# clock.net
KiCad netlist of a schematic drawn in EAGLE
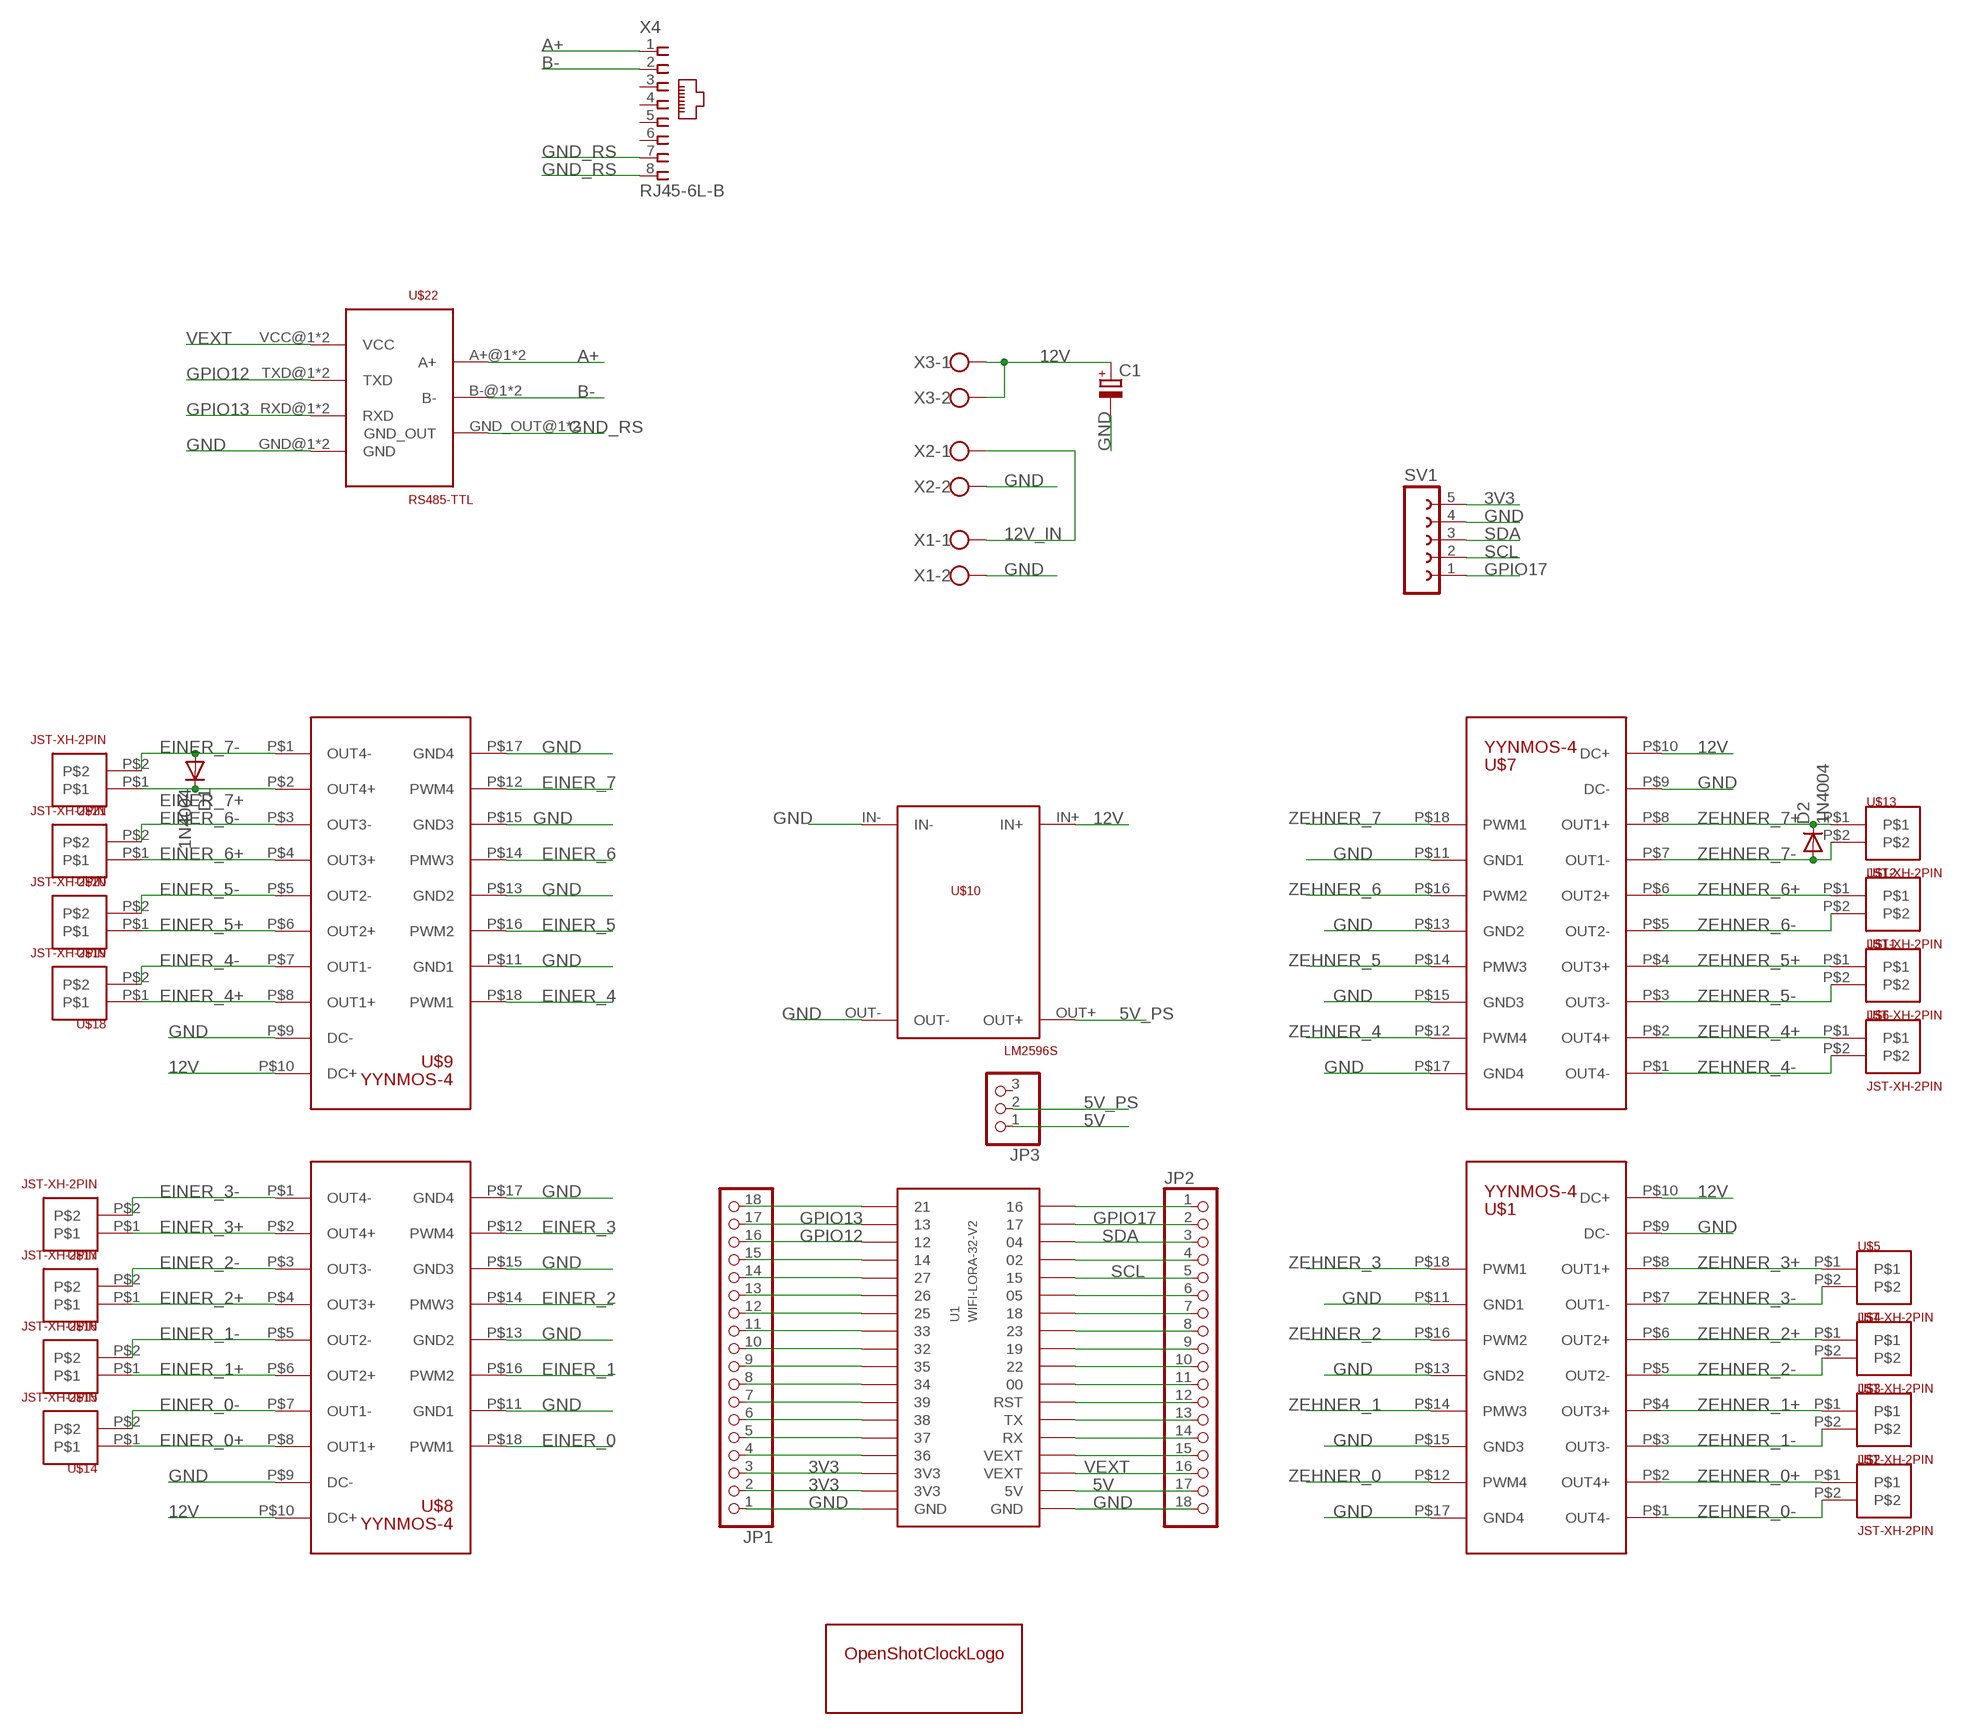
[diagram p0: schematic, sheet 1, part 1 of 2]
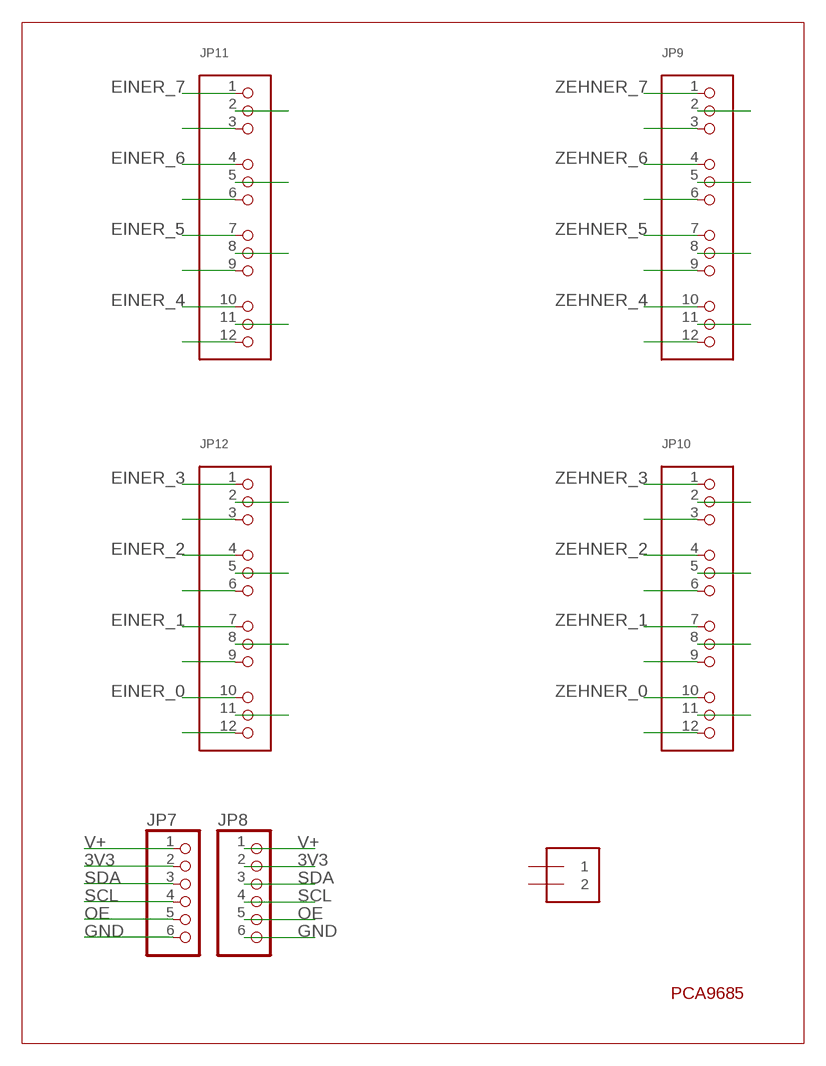
[diagram p1: schematic, sheet 1, part 2 of 2]

(export (version "E")
  (design (tool "Eeschema 10.0.6"))
  (components
    (comp (ref "C1")
      (value "CPOL-EUE2.5-6")
      (footprint "eagle-import:E2,5-6")
      (libsource (lib "eagle-import") (part "CPOL-EUE2.5-6"))
    )
    (comp (ref "D1")
      (value "1N4004")
      (footprint "eagle-import:DO41-10")
      (libsource (lib "eagle-import") (part "1N4004"))
    )
    (comp (ref "D2")
      (value "1N4004")
      (footprint "eagle-import:DO41-10")
      (libsource (lib "eagle-import") (part "1N4004"))
    )
    (comp (ref "J2")
      (value "TERMBLOCK_1X2-3.5MM")
      (footprint "eagle-import:1X2-3.5MM")
      (libsource (lib "eagle-import") (part "TERMBLOCK_1X2-3.5MM"))
    )
    (comp (ref "JP1")
      (value "PINHD-1X18")
      (footprint "eagle-import:1X18")
      (libsource (lib "eagle-import") (part "PINHD-1X18"))
    )
    (comp (ref "JP2")
      (value "PINHD-1X18")
      (footprint "eagle-import:1X18")
      (libsource (lib "eagle-import") (part "PINHD-1X18"))
    )
    (comp (ref "JP3")
      (value "PINHD-1X3")
      (footprint "eagle-import:1X03")
      (libsource (lib "eagle-import") (part "PINHD-1X3"))
    )
    (comp (ref "JP7")
      (value "PINHD-1X6CB")
      (footprint "eagle-import:1X06-CLEANBIG")
      (libsource (lib "eagle-import") (part "PINHD-1X6CB"))
    )
    (comp (ref "JP8")
      (value "PINHD-1X6CB")
      (footprint "eagle-import:1X06-CLEANBIG")
      (libsource (lib "eagle-import") (part "PINHD-1X6CB"))
    )
    (comp (ref "JP9")
      (value "HEADER-3X04")
      (footprint "eagle-import:3X04")
      (libsource (lib "eagle-import") (part "HEADER-3X04"))
    )
    (comp (ref "JP10")
      (value "HEADER-3X04")
      (footprint "eagle-import:3X04")
      (libsource (lib "eagle-import") (part "HEADER-3X04"))
    )
    (comp (ref "JP11")
      (value "HEADER-3X04")
      (footprint "eagle-import:3X04")
      (libsource (lib "eagle-import") (part "HEADER-3X04"))
    )
    (comp (ref "JP12")
      (value "HEADER-3X04")
      (footprint "eagle-import:3X04")
      (libsource (lib "eagle-import") (part "HEADER-3X04"))
    )
    (comp (ref "SV1")
      (value "FE05-1")
      (footprint "eagle-import:FE05-1")
      (libsource (lib "eagle-import") (part "FE05-1"))
    )
    (comp (ref "U$1")
      (value "YYNMOS-4")
      (footprint "eagle-import:YYNMOS-4")
      (libsource (lib "eagle-import") (part "YYNMOS-4"))
    )
    (comp (ref "U$2")
      (value "JST-XH-2PIN")
      (footprint "eagle-import:JST-XH-2PIN")
      (libsource (lib "eagle-import") (part "JST-XH-2PIN"))
    )
    (comp (ref "U$3")
      (value "JST-XH-2PIN")
      (footprint "eagle-import:JST-XH-2PIN")
      (libsource (lib "eagle-import") (part "JST-XH-2PIN"))
    )
    (comp (ref "U$4")
      (value "JST-XH-2PIN")
      (footprint "eagle-import:JST-XH-2PIN")
      (libsource (lib "eagle-import") (part "JST-XH-2PIN"))
    )
    (comp (ref "U$5")
      (value "JST-XH-2PIN")
      (footprint "eagle-import:JST-XH-2PIN")
      (libsource (lib "eagle-import") (part "JST-XH-2PIN"))
    )
    (comp (ref "U$6")
      (value "JST-XH-2PIN")
      (footprint "eagle-import:JST-XH-2PIN")
      (libsource (lib "eagle-import") (part "JST-XH-2PIN"))
    )
    (comp (ref "U$7")
      (value "YYNMOS-4")
      (footprint "eagle-import:YYNMOS-4")
      (libsource (lib "eagle-import") (part "YYNMOS-4"))
    )
    (comp (ref "U$8")
      (value "YYNMOS-4")
      (footprint "eagle-import:YYNMOS-4")
      (libsource (lib "eagle-import") (part "YYNMOS-4"))
    )
    (comp (ref "U$9")
      (value "YYNMOS-4")
      (footprint "eagle-import:YYNMOS-4")
      (libsource (lib "eagle-import") (part "YYNMOS-4"))
    )
    (comp (ref "U$10")
      (value "LM2596S")
      (footprint "eagle-import:LM2596S")
      (libsource (lib "eagle-import") (part "LM2596S"))
    )
    (comp (ref "U$11")
      (value "JST-XH-2PIN")
      (footprint "eagle-import:JST-XH-2PIN")
      (libsource (lib "eagle-import") (part "JST-XH-2PIN"))
    )
    (comp (ref "U$12")
      (value "JST-XH-2PIN")
      (footprint "eagle-import:JST-XH-2PIN")
      (libsource (lib "eagle-import") (part "JST-XH-2PIN"))
    )
    (comp (ref "U$13")
      (value "JST-XH-2PIN")
      (footprint "eagle-import:JST-XH-2PIN")
      (libsource (lib "eagle-import") (part "JST-XH-2PIN"))
    )
    (comp (ref "U$14")
      (value "JST-XH-2PIN")
      (footprint "eagle-import:JST-XH-2PIN")
      (libsource (lib "eagle-import") (part "JST-XH-2PIN"))
    )
    (comp (ref "U$15")
      (value "JST-XH-2PIN")
      (footprint "eagle-import:JST-XH-2PIN")
      (libsource (lib "eagle-import") (part "JST-XH-2PIN"))
    )
    (comp (ref "U$16")
      (value "JST-XH-2PIN")
      (footprint "eagle-import:JST-XH-2PIN")
      (libsource (lib "eagle-import") (part "JST-XH-2PIN"))
    )
    (comp (ref "U$17")
      (value "JST-XH-2PIN")
      (footprint "eagle-import:JST-XH-2PIN")
      (libsource (lib "eagle-import") (part "JST-XH-2PIN"))
    )
    (comp (ref "U$18")
      (value "JST-XH-2PIN")
      (footprint "eagle-import:JST-XH-2PIN")
      (libsource (lib "eagle-import") (part "JST-XH-2PIN"))
    )
    (comp (ref "U$19")
      (value "JST-XH-2PIN")
      (footprint "eagle-import:JST-XH-2PIN")
      (libsource (lib "eagle-import") (part "JST-XH-2PIN"))
    )
    (comp (ref "U$20")
      (value "JST-XH-2PIN")
      (footprint "eagle-import:JST-XH-2PIN")
      (libsource (lib "eagle-import") (part "JST-XH-2PIN"))
    )
    (comp (ref "U$21")
      (value "JST-XH-2PIN")
      (footprint "eagle-import:JST-XH-2PIN")
      (libsource (lib "eagle-import") (part "JST-XH-2PIN"))
    )
    (comp (ref "U$22")
      (value "RS485-TTL")
      (footprint "eagle-import:RS485-TTL")
      (libsource (lib "eagle-import") (part "RS485-TTL"))
    )
    (comp (ref "U$23")
      (value "OPEN-SHOT-CLOCK-LOGO")
      (footprint "eagle-import:OPEN-SHOT-CLOCK-LOGO")
      (libsource (lib "eagle-import") (part "OPEN-SHOT-CLOCK-LOGO"))
    )
    (comp (ref "U1")
      (value "WIFI-LORA-32-V2")
      (footprint "eagle-import:2.54MM_2X18")
      (libsource (lib "eagle-import") (part "WIFI-LORA-32-V2"))
    )
    (comp (ref "X1")
      (value "W237-102")
      (footprint "eagle-import:W237-102")
      (fields (field (name "MPN") "237-102"))
      (libsource (lib "eagle-import") (part "W237-102"))
    )
    (comp (ref "X2")
      (value "W237-102")
      (footprint "eagle-import:W237-102")
      (fields (field (name "MPN") "237-102"))
      (libsource (lib "eagle-import") (part "W237-102"))
    )
    (comp (ref "X3")
      (value "W237-102")
      (footprint "eagle-import:W237-102")
      (fields (field (name "MPN") "237-102"))
      (libsource (lib "eagle-import") (part "W237-102"))
    )
    (comp (ref "X4")
      (value "RJ45-6L-B")
      (footprint "eagle-import:RJ45-NO-SHIELD")
      (libsource (lib "eagle-import") (part "RJ45-6L-B"))
    )
  )
  (nets
    (net (code "1") (name "/3V3") (class "Default")
      (node (ref "JP1") (pin "2") (pinfunction "2_2") (pintype "passive"))
      (node (ref "JP1") (pin "3") (pinfunction "3_3") (pintype "passive"))
      (node (ref "JP7") (pin "2") (pinfunction "2_2") (pintype "passive"))
      (node (ref "JP8") (pin "2") (pinfunction "2_2") (pintype "passive"))
      (node (ref "SV1") (pin "5") (pinfunction "5_5") (pintype "passive"))
      (node (ref "U1") (pin "P$34") (pinfunction "3V3_P$34") (pintype "power_in"))
      (node (ref "U1") (pin "P$35") (pinfunction "3V3_P$35") (pintype "power_in"))
    )
    (net (code "2") (name "/5V") (class "Default")
      (node (ref "JP2") (pin "17") (pinfunction "17_17") (pintype "passive"))
      (node (ref "JP3") (pin "1") (pinfunction "1_1") (pintype "passive"))
      (node (ref "U1") (pin "P$2") (pinfunction "5V_P$2") (pintype "power_in"))
    )
    (net (code "3") (name "/5V_PS") (class "Default")
      (node (ref "JP3") (pin "2") (pinfunction "2_2") (pintype "passive"))
      (node (ref "U$10") (pin "OUT+") (pinfunction "OUT+_OUT+") (pintype "bidirectional"))
    )
    (net (code "4") (name "/12V") (class "Default")
      (node (ref "C1") (pin "+") (pinfunction "+_+") (pintype "passive"))
      (node (ref "U$1") (pin "P$10") (pinfunction "DC+_P$10") (pintype "bidirectional"))
      (node (ref "U$10") (pin "IN+") (pinfunction "IN+_IN+") (pintype "bidirectional"))
      (node (ref "U$7") (pin "P$10") (pinfunction "DC+_P$10") (pintype "bidirectional"))
      (node (ref "U$8") (pin "P$10") (pinfunction "DC+_P$10") (pintype "bidirectional"))
      (node (ref "U$9") (pin "P$10") (pinfunction "DC+_P$10") (pintype "bidirectional"))
      (node (ref "X3") (pin "1") (pinfunction "KL_1") (pintype "passive"))
      (node (ref "X3") (pin "2") (pinfunction "KL_2") (pintype "passive"))
    )
    (net (code "5") (name "/12V_IN") (class "Default")
      (node (ref "X1") (pin "1") (pinfunction "KL_1") (pintype "passive"))
      (node (ref "X2") (pin "1") (pinfunction "KL_1") (pintype "passive"))
    )
    (net (code "6") (name "/A+") (class "Default")
      (node (ref "U$22") (pin "A+@1") (pinfunction "A+_A+@1") (pintype "bidirectional"))
      (node (ref "U$22") (pin "A+@2") (pinfunction "A+_A+@2") (pintype "bidirectional"))
      (node (ref "X4") (pin "1") (pinfunction "1_1") (pintype "passive"))
    )
    (net (code "7") (name "/B-") (class "Default")
      (node (ref "U$22") (pin "B-@1") (pinfunction "B-_B-@1") (pintype "bidirectional"))
      (node (ref "U$22") (pin "B-@2") (pinfunction "B-_B-@2") (pintype "bidirectional"))
      (node (ref "X4") (pin "2") (pinfunction "2_2") (pintype "passive"))
    )
    (net (code "8") (name "/EINER_0") (class "Default")
      (node (ref "JP12") (pin "10") (pinfunction "10_10") (pintype "passive"))
      (node (ref "U$8") (pin "P$18") (pinfunction "PWM1_P$18") (pintype "bidirectional"))
    )
    (net (code "9") (name "/EINER_0+") (class "Default")
      (node (ref "U$14") (pin "P$1") (pinfunction "P$1_P$1") (pintype "bidirectional"))
      (node (ref "U$8") (pin "P$8") (pinfunction "OUT1+_P$8") (pintype "bidirectional"))
    )
    (net (code "10") (name "/EINER_0-") (class "Default")
      (node (ref "U$14") (pin "P$2") (pinfunction "P$2_P$2") (pintype "bidirectional"))
      (node (ref "U$8") (pin "P$7") (pinfunction "OUT1-_P$7") (pintype "bidirectional"))
    )
    (net (code "11") (name "/EINER_1") (class "Default")
      (node (ref "JP12") (pin "7") (pinfunction "7_7") (pintype "passive"))
      (node (ref "U$8") (pin "P$16") (pinfunction "PWM2_P$16") (pintype "bidirectional"))
    )
    (net (code "12") (name "/EINER_1+") (class "Default")
      (node (ref "U$15") (pin "P$1") (pinfunction "P$1_P$1") (pintype "bidirectional"))
      (node (ref "U$8") (pin "P$6") (pinfunction "OUT2+_P$6") (pintype "bidirectional"))
    )
    (net (code "13") (name "/EINER_1-") (class "Default")
      (node (ref "U$15") (pin "P$2") (pinfunction "P$2_P$2") (pintype "bidirectional"))
      (node (ref "U$8") (pin "P$5") (pinfunction "OUT2-_P$5") (pintype "bidirectional"))
    )
    (net (code "14") (name "/EINER_2") (class "Default")
      (node (ref "JP12") (pin "4") (pinfunction "4_4") (pintype "passive"))
      (node (ref "U$8") (pin "P$14") (pinfunction "PMW3_P$14") (pintype "bidirectional"))
    )
    (net (code "15") (name "/EINER_2+") (class "Default")
      (node (ref "U$16") (pin "P$1") (pinfunction "P$1_P$1") (pintype "bidirectional"))
      (node (ref "U$8") (pin "P$4") (pinfunction "OUT3+_P$4") (pintype "bidirectional"))
    )
    (net (code "16") (name "/EINER_2-") (class "Default")
      (node (ref "U$16") (pin "P$2") (pinfunction "P$2_P$2") (pintype "bidirectional"))
      (node (ref "U$8") (pin "P$3") (pinfunction "OUT3-_P$3") (pintype "bidirectional"))
    )
    (net (code "17") (name "/EINER_3") (class "Default")
      (node (ref "JP12") (pin "1") (pinfunction "1_1") (pintype "passive"))
      (node (ref "U$8") (pin "P$12") (pinfunction "PWM4_P$12") (pintype "bidirectional"))
    )
    (net (code "18") (name "/EINER_3+") (class "Default")
      (node (ref "U$17") (pin "P$1") (pinfunction "P$1_P$1") (pintype "bidirectional"))
      (node (ref "U$8") (pin "P$2") (pinfunction "OUT4+_P$2") (pintype "bidirectional"))
    )
    (net (code "19") (name "/EINER_3-") (class "Default")
      (node (ref "U$17") (pin "P$2") (pinfunction "P$2_P$2") (pintype "bidirectional"))
      (node (ref "U$8") (pin "P$1") (pinfunction "OUT4-_P$1") (pintype "bidirectional"))
    )
    (net (code "20") (name "/EINER_4") (class "Default")
      (node (ref "JP11") (pin "10") (pinfunction "10_10") (pintype "passive"))
      (node (ref "U$9") (pin "P$18") (pinfunction "PWM1_P$18") (pintype "bidirectional"))
    )
    (net (code "21") (name "/EINER_4+") (class "Default")
      (node (ref "U$18") (pin "P$1") (pinfunction "P$1_P$1") (pintype "bidirectional"))
      (node (ref "U$9") (pin "P$8") (pinfunction "OUT1+_P$8") (pintype "bidirectional"))
    )
    (net (code "22") (name "/EINER_4-") (class "Default")
      (node (ref "U$18") (pin "P$2") (pinfunction "P$2_P$2") (pintype "bidirectional"))
      (node (ref "U$9") (pin "P$7") (pinfunction "OUT1-_P$7") (pintype "bidirectional"))
    )
    (net (code "23") (name "/EINER_5") (class "Default")
      (node (ref "JP11") (pin "7") (pinfunction "7_7") (pintype "passive"))
      (node (ref "U$9") (pin "P$16") (pinfunction "PWM2_P$16") (pintype "bidirectional"))
    )
    (net (code "24") (name "/EINER_5+") (class "Default")
      (node (ref "U$19") (pin "P$1") (pinfunction "P$1_P$1") (pintype "bidirectional"))
      (node (ref "U$9") (pin "P$6") (pinfunction "OUT2+_P$6") (pintype "bidirectional"))
    )
    (net (code "25") (name "/EINER_5-") (class "Default")
      (node (ref "U$19") (pin "P$2") (pinfunction "P$2_P$2") (pintype "bidirectional"))
      (node (ref "U$9") (pin "P$5") (pinfunction "OUT2-_P$5") (pintype "bidirectional"))
    )
    (net (code "26") (name "/EINER_6") (class "Default")
      (node (ref "JP11") (pin "4") (pinfunction "4_4") (pintype "passive"))
      (node (ref "U$9") (pin "P$14") (pinfunction "PMW3_P$14") (pintype "bidirectional"))
    )
    (net (code "27") (name "/EINER_6+") (class "Default")
      (node (ref "U$20") (pin "P$1") (pinfunction "P$1_P$1") (pintype "bidirectional"))
      (node (ref "U$9") (pin "P$4") (pinfunction "OUT3+_P$4") (pintype "bidirectional"))
    )
    (net (code "28") (name "/EINER_6-") (class "Default")
      (node (ref "U$20") (pin "P$2") (pinfunction "P$2_P$2") (pintype "bidirectional"))
      (node (ref "U$9") (pin "P$3") (pinfunction "OUT3-_P$3") (pintype "bidirectional"))
    )
    (net (code "29") (name "/EINER_7") (class "Default")
      (node (ref "JP11") (pin "1") (pinfunction "1_1") (pintype "passive"))
      (node (ref "U$9") (pin "P$12") (pinfunction "PWM4_P$12") (pintype "bidirectional"))
    )
    (net (code "30") (name "/EINER_7+") (class "Default")
      (node (ref "D1") (pin "C") (pinfunction "C_C") (pintype "passive"))
      (node (ref "U$21") (pin "P$1") (pinfunction "P$1_P$1") (pintype "bidirectional"))
      (node (ref "U$9") (pin "P$2") (pinfunction "OUT4+_P$2") (pintype "bidirectional"))
    )
    (net (code "31") (name "/EINER_7-") (class "Default")
      (node (ref "D1") (pin "A") (pinfunction "A_A") (pintype "passive"))
      (node (ref "U$21") (pin "P$2") (pinfunction "P$2_P$2") (pintype "bidirectional"))
      (node (ref "U$9") (pin "P$1") (pinfunction "OUT4-_P$1") (pintype "bidirectional"))
    )
    (net (code "32") (name "/GND") (class "Default")
      (node (ref "C1") (pin "-") (pinfunction "-_-") (pintype "passive"))
      (node (ref "JP1") (pin "1") (pinfunction "1_1") (pintype "passive"))
      (node (ref "JP2") (pin "18") (pinfunction "18_18") (pintype "passive"))
      (node (ref "JP7") (pin "6") (pinfunction "6_6") (pintype "passive"))
      (node (ref "JP8") (pin "6") (pinfunction "6_6") (pintype "passive"))
      (node (ref "SV1") (pin "4") (pinfunction "4_4") (pintype "passive"))
      (node (ref "U$1") (pin "P$11") (pinfunction "GND1_P$11") (pintype "bidirectional"))
      (node (ref "U$1") (pin "P$13") (pinfunction "GND2_P$13") (pintype "bidirectional"))
      (node (ref "U$1") (pin "P$15") (pinfunction "GND3_P$15") (pintype "bidirectional"))
      (node (ref "U$1") (pin "P$17") (pinfunction "GND4_P$17") (pintype "bidirectional"))
      (node (ref "U$1") (pin "P$9") (pinfunction "DC-_P$9") (pintype "bidirectional"))
      (node (ref "U$10") (pin "IN-") (pinfunction "IN-_IN-") (pintype "bidirectional"))
      (node (ref "U$10") (pin "OUT-") (pinfunction "OUT-_OUT-") (pintype "bidirectional"))
      (node (ref "U$22") (pin "GND@1") (pinfunction "GND_GND@1") (pintype "bidirectional"))
      (node (ref "U$22") (pin "GND@2") (pinfunction "GND_GND@2") (pintype "bidirectional"))
      (node (ref "U$7") (pin "P$11") (pinfunction "GND1_P$11") (pintype "bidirectional"))
      (node (ref "U$7") (pin "P$13") (pinfunction "GND2_P$13") (pintype "bidirectional"))
      (node (ref "U$7") (pin "P$15") (pinfunction "GND3_P$15") (pintype "bidirectional"))
      (node (ref "U$7") (pin "P$17") (pinfunction "GND4_P$17") (pintype "bidirectional"))
      (node (ref "U$7") (pin "P$9") (pinfunction "DC-_P$9") (pintype "bidirectional"))
      (node (ref "U$8") (pin "P$11") (pinfunction "GND1_P$11") (pintype "bidirectional"))
      (node (ref "U$8") (pin "P$13") (pinfunction "GND2_P$13") (pintype "bidirectional"))
      (node (ref "U$8") (pin "P$15") (pinfunction "GND3_P$15") (pintype "bidirectional"))
      (node (ref "U$8") (pin "P$17") (pinfunction "GND4_P$17") (pintype "bidirectional"))
      (node (ref "U$8") (pin "P$9") (pinfunction "DC-_P$9") (pintype "bidirectional"))
      (node (ref "U$9") (pin "P$11") (pinfunction "GND1_P$11") (pintype "bidirectional"))
      (node (ref "U$9") (pin "P$13") (pinfunction "GND2_P$13") (pintype "bidirectional"))
      (node (ref "U$9") (pin "P$15") (pinfunction "GND3_P$15") (pintype "bidirectional"))
      (node (ref "U$9") (pin "P$17") (pinfunction "GND4_P$17") (pintype "bidirectional"))
      (node (ref "U$9") (pin "P$9") (pinfunction "DC-_P$9") (pintype "bidirectional"))
      (node (ref "U1") (pin "P$1") (pinfunction "GND_P$1") (pintype "power_in"))
      (node (ref "U1") (pin "P$36") (pinfunction "GND_P$36") (pintype "power_in"))
      (node (ref "X1") (pin "2") (pinfunction "KL_2") (pintype "passive"))
      (node (ref "X2") (pin "2") (pinfunction "KL_2") (pintype "passive"))
    )
    (net (code "33") (name "/GND_RS") (class "Default")
      (node (ref "U$22") (pin "GND_OUT@1") (pinfunction "GND_OUT_GND_OUT@1") (pintype "bidirectional"))
      (node (ref "U$22") (pin "GND_OUT@2") (pinfunction "GND_OUT_GND_OUT@2") (pintype "bidirectional"))
      (node (ref "X4") (pin "7") (pinfunction "7_7") (pintype "passive"))
      (node (ref "X4") (pin "8") (pinfunction "8_8") (pintype "passive"))
    )
    (net (code "34") (name "/GPIO12") (class "Default")
      (node (ref "JP1") (pin "16") (pinfunction "16_16") (pintype "passive"))
      (node (ref "U$22") (pin "TXD@1") (pinfunction "TXD_TXD@1") (pintype "bidirectional"))
      (node (ref "U$22") (pin "TXD@2") (pinfunction "TXD_TXD@2") (pintype "bidirectional"))
      (node (ref "U1") (pin "P$21") (pinfunction "12_P$21") (pintype "bidirectional"))
    )
    (net (code "35") (name "/GPIO13") (class "Default")
      (node (ref "JP1") (pin "17") (pinfunction "17_17") (pintype "passive"))
      (node (ref "U$22") (pin "RXD@1") (pinfunction "RXD_RXD@1") (pintype "bidirectional"))
      (node (ref "U$22") (pin "RXD@2") (pinfunction "RXD_RXD@2") (pintype "bidirectional"))
      (node (ref "U1") (pin "P$20") (pinfunction "13_P$20") (pintype "bidirectional"))
    )
    (net (code "36") (name "/GPIO17") (class "Default")
      (node (ref "JP2") (pin "2") (pinfunction "2_2") (pintype "passive"))
      (node (ref "SV1") (pin "1") (pinfunction "1_1") (pintype "passive"))
      (node (ref "U1") (pin "P$17") (pinfunction "17_P$17") (pintype "bidirectional"))
    )
    (net (code "37") (name "/OE") (class "Default")
      (node (ref "JP7") (pin "5") (pinfunction "5_5") (pintype "passive"))
      (node (ref "JP8") (pin "5") (pinfunction "5_5") (pintype "passive"))
    )
    (net (code "38") (name "/SCL") (class "Default")
      (node (ref "JP2") (pin "5") (pinfunction "5_5") (pintype "passive"))
      (node (ref "JP7") (pin "4") (pinfunction "4_4") (pintype "passive"))
      (node (ref "JP8") (pin "4") (pinfunction "4_4") (pintype "passive"))
      (node (ref "SV1") (pin "2") (pinfunction "2_2") (pintype "passive"))
      (node (ref "U1") (pin "P$14") (pinfunction "15_P$14") (pintype "bidirectional"))
    )
    (net (code "39") (name "/SDA") (class "Default")
      (node (ref "JP2") (pin "3") (pinfunction "3_3") (pintype "passive"))
      (node (ref "JP7") (pin "3") (pinfunction "3_3") (pintype "passive"))
      (node (ref "JP8") (pin "3") (pinfunction "3_3") (pintype "passive"))
      (node (ref "SV1") (pin "3") (pinfunction "3_3") (pintype "passive"))
      (node (ref "U1") (pin "P$16") (pinfunction "04_P$16") (pintype "bidirectional"))
    )
    (net (code "40") (name "/V+") (class "Default")
      (node (ref "JP7") (pin "1") (pinfunction "1_1") (pintype "passive"))
      (node (ref "JP8") (pin "1") (pinfunction "1_1") (pintype "passive"))
    )
    (net (code "41") (name "/VEXT") (class "Default")
      (node (ref "JP2") (pin "16") (pinfunction "16_16") (pintype "passive"))
      (node (ref "U$22") (pin "VCC@1") (pinfunction "VCC_VCC@1") (pintype "bidirectional"))
      (node (ref "U$22") (pin "VCC@2") (pinfunction "VCC_VCC@2") (pintype "bidirectional"))
      (node (ref "U1") (pin "P$3") (pinfunction "VEXT_P$3") (pintype "power_in"))
    )
    (net (code "42") (name "/ZEHNER_0") (class "Default")
      (node (ref "JP10") (pin "10") (pinfunction "10_10") (pintype "passive"))
      (node (ref "U$1") (pin "P$12") (pinfunction "PWM4_P$12") (pintype "bidirectional"))
    )
    (net (code "43") (name "/ZEHNER_0+") (class "Default")
      (node (ref "U$1") (pin "P$2") (pinfunction "OUT4+_P$2") (pintype "bidirectional"))
      (node (ref "U$2") (pin "P$1") (pinfunction "P$1_P$1") (pintype "bidirectional"))
    )
    (net (code "44") (name "/ZEHNER_0-") (class "Default")
      (node (ref "U$1") (pin "P$1") (pinfunction "OUT4-_P$1") (pintype "bidirectional"))
      (node (ref "U$2") (pin "P$2") (pinfunction "P$2_P$2") (pintype "bidirectional"))
    )
    (net (code "45") (name "/ZEHNER_1") (class "Default")
      (node (ref "JP10") (pin "7") (pinfunction "7_7") (pintype "passive"))
      (node (ref "U$1") (pin "P$14") (pinfunction "PMW3_P$14") (pintype "bidirectional"))
    )
    (net (code "46") (name "/ZEHNER_1+") (class "Default")
      (node (ref "U$1") (pin "P$4") (pinfunction "OUT3+_P$4") (pintype "bidirectional"))
      (node (ref "U$3") (pin "P$1") (pinfunction "P$1_P$1") (pintype "bidirectional"))
    )
    (net (code "47") (name "/ZEHNER_1-") (class "Default")
      (node (ref "U$1") (pin "P$3") (pinfunction "OUT3-_P$3") (pintype "bidirectional"))
      (node (ref "U$3") (pin "P$2") (pinfunction "P$2_P$2") (pintype "bidirectional"))
    )
    (net (code "48") (name "/ZEHNER_2") (class "Default")
      (node (ref "JP10") (pin "4") (pinfunction "4_4") (pintype "passive"))
      (node (ref "U$1") (pin "P$16") (pinfunction "PWM2_P$16") (pintype "bidirectional"))
    )
    (net (code "49") (name "/ZEHNER_2+") (class "Default")
      (node (ref "U$1") (pin "P$6") (pinfunction "OUT2+_P$6") (pintype "bidirectional"))
      (node (ref "U$4") (pin "P$1") (pinfunction "P$1_P$1") (pintype "bidirectional"))
    )
    (net (code "50") (name "/ZEHNER_2-") (class "Default")
      (node (ref "U$1") (pin "P$5") (pinfunction "OUT2-_P$5") (pintype "bidirectional"))
      (node (ref "U$4") (pin "P$2") (pinfunction "P$2_P$2") (pintype "bidirectional"))
    )
    (net (code "51") (name "/ZEHNER_3") (class "Default")
      (node (ref "JP10") (pin "1") (pinfunction "1_1") (pintype "passive"))
      (node (ref "U$1") (pin "P$18") (pinfunction "PWM1_P$18") (pintype "bidirectional"))
    )
    (net (code "52") (name "/ZEHNER_3+") (class "Default")
      (node (ref "U$1") (pin "P$8") (pinfunction "OUT1+_P$8") (pintype "bidirectional"))
      (node (ref "U$5") (pin "P$1") (pinfunction "P$1_P$1") (pintype "bidirectional"))
    )
    (net (code "53") (name "/ZEHNER_3-") (class "Default")
      (node (ref "U$1") (pin "P$7") (pinfunction "OUT1-_P$7") (pintype "bidirectional"))
      (node (ref "U$5") (pin "P$2") (pinfunction "P$2_P$2") (pintype "bidirectional"))
    )
    (net (code "54") (name "/ZEHNER_4") (class "Default")
      (node (ref "JP9") (pin "10") (pinfunction "10_10") (pintype "passive"))
      (node (ref "U$7") (pin "P$12") (pinfunction "PWM4_P$12") (pintype "bidirectional"))
    )
    (net (code "55") (name "/ZEHNER_4+") (class "Default")
      (node (ref "U$6") (pin "P$1") (pinfunction "P$1_P$1") (pintype "bidirectional"))
      (node (ref "U$7") (pin "P$2") (pinfunction "OUT4+_P$2") (pintype "bidirectional"))
    )
    (net (code "56") (name "/ZEHNER_4-") (class "Default")
      (node (ref "U$6") (pin "P$2") (pinfunction "P$2_P$2") (pintype "bidirectional"))
      (node (ref "U$7") (pin "P$1") (pinfunction "OUT4-_P$1") (pintype "bidirectional"))
    )
    (net (code "57") (name "/ZEHNER_5") (class "Default")
      (node (ref "JP9") (pin "7") (pinfunction "7_7") (pintype "passive"))
      (node (ref "U$7") (pin "P$14") (pinfunction "PMW3_P$14") (pintype "bidirectional"))
    )
    (net (code "58") (name "/ZEHNER_5+") (class "Default")
      (node (ref "U$11") (pin "P$1") (pinfunction "P$1_P$1") (pintype "bidirectional"))
      (node (ref "U$7") (pin "P$4") (pinfunction "OUT3+_P$4") (pintype "bidirectional"))
    )
    (net (code "59") (name "/ZEHNER_5-") (class "Default")
      (node (ref "U$11") (pin "P$2") (pinfunction "P$2_P$2") (pintype "bidirectional"))
      (node (ref "U$7") (pin "P$3") (pinfunction "OUT3-_P$3") (pintype "bidirectional"))
    )
    (net (code "60") (name "/ZEHNER_6") (class "Default")
      (node (ref "JP9") (pin "4") (pinfunction "4_4") (pintype "passive"))
      (node (ref "U$7") (pin "P$16") (pinfunction "PWM2_P$16") (pintype "bidirectional"))
    )
    (net (code "61") (name "/ZEHNER_6+") (class "Default")
      (node (ref "U$12") (pin "P$1") (pinfunction "P$1_P$1") (pintype "bidirectional"))
      (node (ref "U$7") (pin "P$6") (pinfunction "OUT2+_P$6") (pintype "bidirectional"))
    )
    (net (code "62") (name "/ZEHNER_6-") (class "Default")
      (node (ref "U$12") (pin "P$2") (pinfunction "P$2_P$2") (pintype "bidirectional"))
      (node (ref "U$7") (pin "P$5") (pinfunction "OUT2-_P$5") (pintype "bidirectional"))
    )
    (net (code "63") (name "/ZEHNER_7") (class "Default")
      (node (ref "JP9") (pin "1") (pinfunction "1_1") (pintype "passive"))
      (node (ref "U$7") (pin "P$18") (pinfunction "PWM1_P$18") (pintype "bidirectional"))
    )
    (net (code "64") (name "/ZEHNER_7+") (class "Default")
      (node (ref "D2") (pin "C") (pinfunction "C_C") (pintype "passive"))
      (node (ref "U$13") (pin "P$1") (pinfunction "P$1_P$1") (pintype "bidirectional"))
      (node (ref "U$7") (pin "P$8") (pinfunction "OUT1+_P$8") (pintype "bidirectional"))
    )
    (net (code "65") (name "/ZEHNER_7-") (class "Default")
      (node (ref "D2") (pin "A") (pinfunction "A_A") (pintype "passive"))
      (node (ref "U$13") (pin "P$2") (pinfunction "P$2_P$2") (pintype "bidirectional"))
      (node (ref "U$7") (pin "P$7") (pinfunction "OUT1-_P$7") (pintype "bidirectional"))
    )
    (net (code "66") (name "Net-(JP2-Pad15)") (class "Default")
      (node (ref "JP2") (pin "15") (pinfunction "15_15") (pintype "passive"))
      (node (ref "U1") (pin "P$4") (pinfunction "VEXT_P$4") (pintype "bidirectional"))
    )
    (net (code "67") (name "Net-(U1-00)") (class "Default")
      (node (ref "JP2") (pin "11") (pinfunction "11_11") (pintype "passive"))
      (node (ref "U1") (pin "P$8") (pinfunction "00_P$8") (pintype "bidirectional"))
    )
    (net (code "68") (name "Net-(U1-02)") (class "Default")
      (node (ref "JP2") (pin "4") (pinfunction "4_4") (pintype "passive"))
      (node (ref "U1") (pin "P$15") (pinfunction "02_P$15") (pintype "bidirectional"))
    )
    (net (code "69") (name "Net-(U1-05)") (class "Default")
      (node (ref "JP2") (pin "6") (pinfunction "6_6") (pintype "passive"))
      (node (ref "U1") (pin "P$13") (pinfunction "05_P$13") (pintype "bidirectional"))
    )
    (net (code "70") (name "Net-(U1-14)") (class "Default")
      (node (ref "JP1") (pin "15") (pinfunction "15_15") (pintype "passive"))
      (node (ref "U1") (pin "P$22") (pinfunction "14_P$22") (pintype "bidirectional"))
    )
    (net (code "71") (name "Net-(U1-16)") (class "Default")
      (node (ref "JP2") (pin "1") (pinfunction "1_1") (pintype "passive"))
      (node (ref "U1") (pin "P$18") (pinfunction "16_P$18") (pintype "bidirectional"))
    )
    (net (code "72") (name "Net-(U1-18)") (class "Default")
      (node (ref "JP2") (pin "7") (pinfunction "7_7") (pintype "passive"))
      (node (ref "U1") (pin "P$12") (pinfunction "18_P$12") (pintype "bidirectional"))
    )
    (net (code "73") (name "Net-(U1-19)") (class "Default")
      (node (ref "JP2") (pin "9") (pinfunction "9_9") (pintype "passive"))
      (node (ref "U1") (pin "P$10") (pinfunction "19_P$10") (pintype "bidirectional"))
    )
    (net (code "74") (name "Net-(U1-21)") (class "Default")
      (node (ref "JP1") (pin "18") (pinfunction "18_18") (pintype "passive"))
      (node (ref "U1") (pin "P$19") (pinfunction "21_P$19") (pintype "bidirectional"))
    )
    (net (code "75") (name "Net-(U1-22)") (class "Default")
      (node (ref "JP2") (pin "10") (pinfunction "10_10") (pintype "passive"))
      (node (ref "U1") (pin "P$9") (pinfunction "22_P$9") (pintype "bidirectional"))
    )
    (net (code "76") (name "Net-(U1-23)") (class "Default")
      (node (ref "JP2") (pin "8") (pinfunction "8_8") (pintype "passive"))
      (node (ref "U1") (pin "P$11") (pinfunction "23_P$11") (pintype "bidirectional"))
    )
    (net (code "77") (name "Net-(U1-25)") (class "Default")
      (node (ref "JP1") (pin "12") (pinfunction "12_12") (pintype "passive"))
      (node (ref "U1") (pin "P$25") (pinfunction "25_P$25") (pintype "bidirectional"))
    )
    (net (code "78") (name "Net-(U1-26)") (class "Default")
      (node (ref "JP1") (pin "13") (pinfunction "13_13") (pintype "passive"))
      (node (ref "U1") (pin "P$24") (pinfunction "26_P$24") (pintype "bidirectional"))
    )
    (net (code "79") (name "Net-(U1-27)") (class "Default")
      (node (ref "JP1") (pin "14") (pinfunction "14_14") (pintype "passive"))
      (node (ref "U1") (pin "P$23") (pinfunction "27_P$23") (pintype "bidirectional"))
    )
    (net (code "80") (name "Net-(U1-32)") (class "Default")
      (node (ref "JP1") (pin "10") (pinfunction "10_10") (pintype "passive"))
      (node (ref "U1") (pin "P$27") (pinfunction "32_P$27") (pintype "bidirectional"))
    )
    (net (code "81") (name "Net-(U1-33)") (class "Default")
      (node (ref "JP1") (pin "11") (pinfunction "11_11") (pintype "passive"))
      (node (ref "U1") (pin "P$26") (pinfunction "33_P$26") (pintype "bidirectional"))
    )
    (net (code "82") (name "Net-(U1-34)") (class "Default")
      (node (ref "JP1") (pin "8") (pinfunction "8_8") (pintype "passive"))
      (node (ref "U1") (pin "P$29") (pinfunction "34_P$29") (pintype "bidirectional"))
    )
    (net (code "83") (name "Net-(U1-35)") (class "Default")
      (node (ref "JP1") (pin "9") (pinfunction "9_9") (pintype "passive"))
      (node (ref "U1") (pin "P$28") (pinfunction "35_P$28") (pintype "bidirectional"))
    )
    (net (code "84") (name "Net-(U1-36)") (class "Default")
      (node (ref "JP1") (pin "4") (pinfunction "4_4") (pintype "passive"))
      (node (ref "U1") (pin "P$33") (pinfunction "36_P$33") (pintype "bidirectional"))
    )
    (net (code "85") (name "Net-(U1-37)") (class "Default")
      (node (ref "JP1") (pin "5") (pinfunction "5_5") (pintype "passive"))
      (node (ref "U1") (pin "P$32") (pinfunction "37_P$32") (pintype "bidirectional"))
    )
    (net (code "86") (name "Net-(U1-38)") (class "Default")
      (node (ref "JP1") (pin "6") (pinfunction "6_6") (pintype "passive"))
      (node (ref "U1") (pin "P$31") (pinfunction "38_P$31") (pintype "bidirectional"))
    )
    (net (code "87") (name "Net-(U1-39)") (class "Default")
      (node (ref "JP1") (pin "7") (pinfunction "7_7") (pintype "passive"))
      (node (ref "U1") (pin "P$30") (pinfunction "39_P$30") (pintype "bidirectional"))
    )
    (net (code "88") (name "Net-(U1-RST)") (class "Default")
      (node (ref "JP2") (pin "12") (pinfunction "12_12") (pintype "passive"))
      (node (ref "U1") (pin "P$7") (pinfunction "RST_P$7") (pintype "bidirectional"))
    )
    (net (code "89") (name "Net-(U1-RX)") (class "Default")
      (node (ref "JP2") (pin "14") (pinfunction "14_14") (pintype "passive"))
      (node (ref "U1") (pin "P$5") (pinfunction "RX_P$5") (pintype "bidirectional"))
    )
    (net (code "90") (name "Net-(U1-TX)") (class "Default")
      (node (ref "JP2") (pin "13") (pinfunction "13_13") (pintype "passive"))
      (node (ref "U1") (pin "P$6") (pinfunction "TX_P$6") (pintype "bidirectional"))
    )
    (net (code "91") (name "unconnected-(J2-Pad1)") (class "Default")
      (node (ref "J2") (pin "1") (pinfunction "1_1") (pintype "passive"))
    )
    (net (code "92") (name "unconnected-(J2-Pad2)") (class "Default")
      (node (ref "J2") (pin "2") (pinfunction "2_2") (pintype "passive"))
    )
    (net (code "93") (name "unconnected-(JP3-Pad3)") (class "Default")
      (node (ref "JP3") (pin "3") (pinfunction "3_3") (pintype "passive"))
    )
    (net (code "94") (name "unconnected-(JP9-Pad2)") (class "Default")
      (node (ref "JP9") (pin "2") (pinfunction "2_2") (pintype "passive"))
    )
    (net (code "95") (name "unconnected-(JP9-Pad3)") (class "Default")
      (node (ref "JP9") (pin "3") (pinfunction "3_3") (pintype "passive"))
    )
    (net (code "96") (name "unconnected-(JP9-Pad5)") (class "Default")
      (node (ref "JP9") (pin "5") (pinfunction "5_5") (pintype "passive"))
    )
    (net (code "97") (name "unconnected-(JP9-Pad6)") (class "Default")
      (node (ref "JP9") (pin "6") (pinfunction "6_6") (pintype "passive"))
    )
    (net (code "98") (name "unconnected-(JP9-Pad8)") (class "Default")
      (node (ref "JP9") (pin "8") (pinfunction "8_8") (pintype "passive"))
    )
    (net (code "99") (name "unconnected-(JP9-Pad9)") (class "Default")
      (node (ref "JP9") (pin "9") (pinfunction "9_9") (pintype "passive"))
    )
    (net (code "100") (name "unconnected-(JP9-Pad11)") (class "Default")
      (node (ref "JP9") (pin "11") (pinfunction "11_11") (pintype "passive"))
    )
    (net (code "101") (name "unconnected-(JP9-Pad12)") (class "Default")
      (node (ref "JP9") (pin "12") (pinfunction "12_12") (pintype "passive"))
    )
    (net (code "102") (name "unconnected-(JP10-Pad2)") (class "Default")
      (node (ref "JP10") (pin "2") (pinfunction "2_2") (pintype "passive"))
    )
    (net (code "103") (name "unconnected-(JP10-Pad3)") (class "Default")
      (node (ref "JP10") (pin "3") (pinfunction "3_3") (pintype "passive"))
    )
    (net (code "104") (name "unconnected-(JP10-Pad5)") (class "Default")
      (node (ref "JP10") (pin "5") (pinfunction "5_5") (pintype "passive"))
    )
    (net (code "105") (name "unconnected-(JP10-Pad6)") (class "Default")
      (node (ref "JP10") (pin "6") (pinfunction "6_6") (pintype "passive"))
    )
    (net (code "106") (name "unconnected-(JP10-Pad8)") (class "Default")
      (node (ref "JP10") (pin "8") (pinfunction "8_8") (pintype "passive"))
    )
    (net (code "107") (name "unconnected-(JP10-Pad9)") (class "Default")
      (node (ref "JP10") (pin "9") (pinfunction "9_9") (pintype "passive"))
    )
    (net (code "108") (name "unconnected-(JP10-Pad11)") (class "Default")
      (node (ref "JP10") (pin "11") (pinfunction "11_11") (pintype "passive"))
    )
    (net (code "109") (name "unconnected-(JP10-Pad12)") (class "Default")
      (node (ref "JP10") (pin "12") (pinfunction "12_12") (pintype "passive"))
    )
    (net (code "110") (name "unconnected-(JP11-Pad2)") (class "Default")
      (node (ref "JP11") (pin "2") (pinfunction "2_2") (pintype "passive"))
    )
    (net (code "111") (name "unconnected-(JP11-Pad3)") (class "Default")
      (node (ref "JP11") (pin "3") (pinfunction "3_3") (pintype "passive"))
    )
    (net (code "112") (name "unconnected-(JP11-Pad5)") (class "Default")
      (node (ref "JP11") (pin "5") (pinfunction "5_5") (pintype "passive"))
    )
    (net (code "113") (name "unconnected-(JP11-Pad6)") (class "Default")
      (node (ref "JP11") (pin "6") (pinfunction "6_6") (pintype "passive"))
    )
    (net (code "114") (name "unconnected-(JP11-Pad8)") (class "Default")
      (node (ref "JP11") (pin "8") (pinfunction "8_8") (pintype "passive"))
    )
    (net (code "115") (name "unconnected-(JP11-Pad9)") (class "Default")
      (node (ref "JP11") (pin "9") (pinfunction "9_9") (pintype "passive"))
    )
    (net (code "116") (name "unconnected-(JP11-Pad11)") (class "Default")
      (node (ref "JP11") (pin "11") (pinfunction "11_11") (pintype "passive"))
    )
    (net (code "117") (name "unconnected-(JP11-Pad12)") (class "Default")
      (node (ref "JP11") (pin "12") (pinfunction "12_12") (pintype "passive"))
    )
    (net (code "118") (name "unconnected-(JP12-Pad2)") (class "Default")
      (node (ref "JP12") (pin "2") (pinfunction "2_2") (pintype "passive"))
    )
    (net (code "119") (name "unconnected-(JP12-Pad3)") (class "Default")
      (node (ref "JP12") (pin "3") (pinfunction "3_3") (pintype "passive"))
    )
    (net (code "120") (name "unconnected-(JP12-Pad5)") (class "Default")
      (node (ref "JP12") (pin "5") (pinfunction "5_5") (pintype "passive"))
    )
    (net (code "121") (name "unconnected-(JP12-Pad6)") (class "Default")
      (node (ref "JP12") (pin "6") (pinfunction "6_6") (pintype "passive"))
    )
    (net (code "122") (name "unconnected-(JP12-Pad8)") (class "Default")
      (node (ref "JP12") (pin "8") (pinfunction "8_8") (pintype "passive"))
    )
    (net (code "123") (name "unconnected-(JP12-Pad9)") (class "Default")
      (node (ref "JP12") (pin "9") (pinfunction "9_9") (pintype "passive"))
    )
    (net (code "124") (name "unconnected-(JP12-Pad11)") (class "Default")
      (node (ref "JP12") (pin "11") (pinfunction "11_11") (pintype "passive"))
    )
    (net (code "125") (name "unconnected-(JP12-Pad12)") (class "Default")
      (node (ref "JP12") (pin "12") (pinfunction "12_12") (pintype "passive"))
    )
    (net (code "126") (name "unconnected-(X4-Pad3)") (class "Default")
      (node (ref "X4") (pin "3") (pinfunction "3_3") (pintype "passive"))
    )
    (net (code "127") (name "unconnected-(X4-Pad4)") (class "Default")
      (node (ref "X4") (pin "4") (pinfunction "4_4") (pintype "passive"))
    )
    (net (code "128") (name "unconnected-(X4-Pad5)") (class "Default")
      (node (ref "X4") (pin "5") (pinfunction "5_5") (pintype "passive"))
    )
    (net (code "129") (name "unconnected-(X4-Pad6)") (class "Default")
      (node (ref "X4") (pin "6") (pinfunction "6_6") (pintype "passive"))
    )
  )
)
